# DAC.net
KiCad netlist of a schematic drawn in Altium Designer
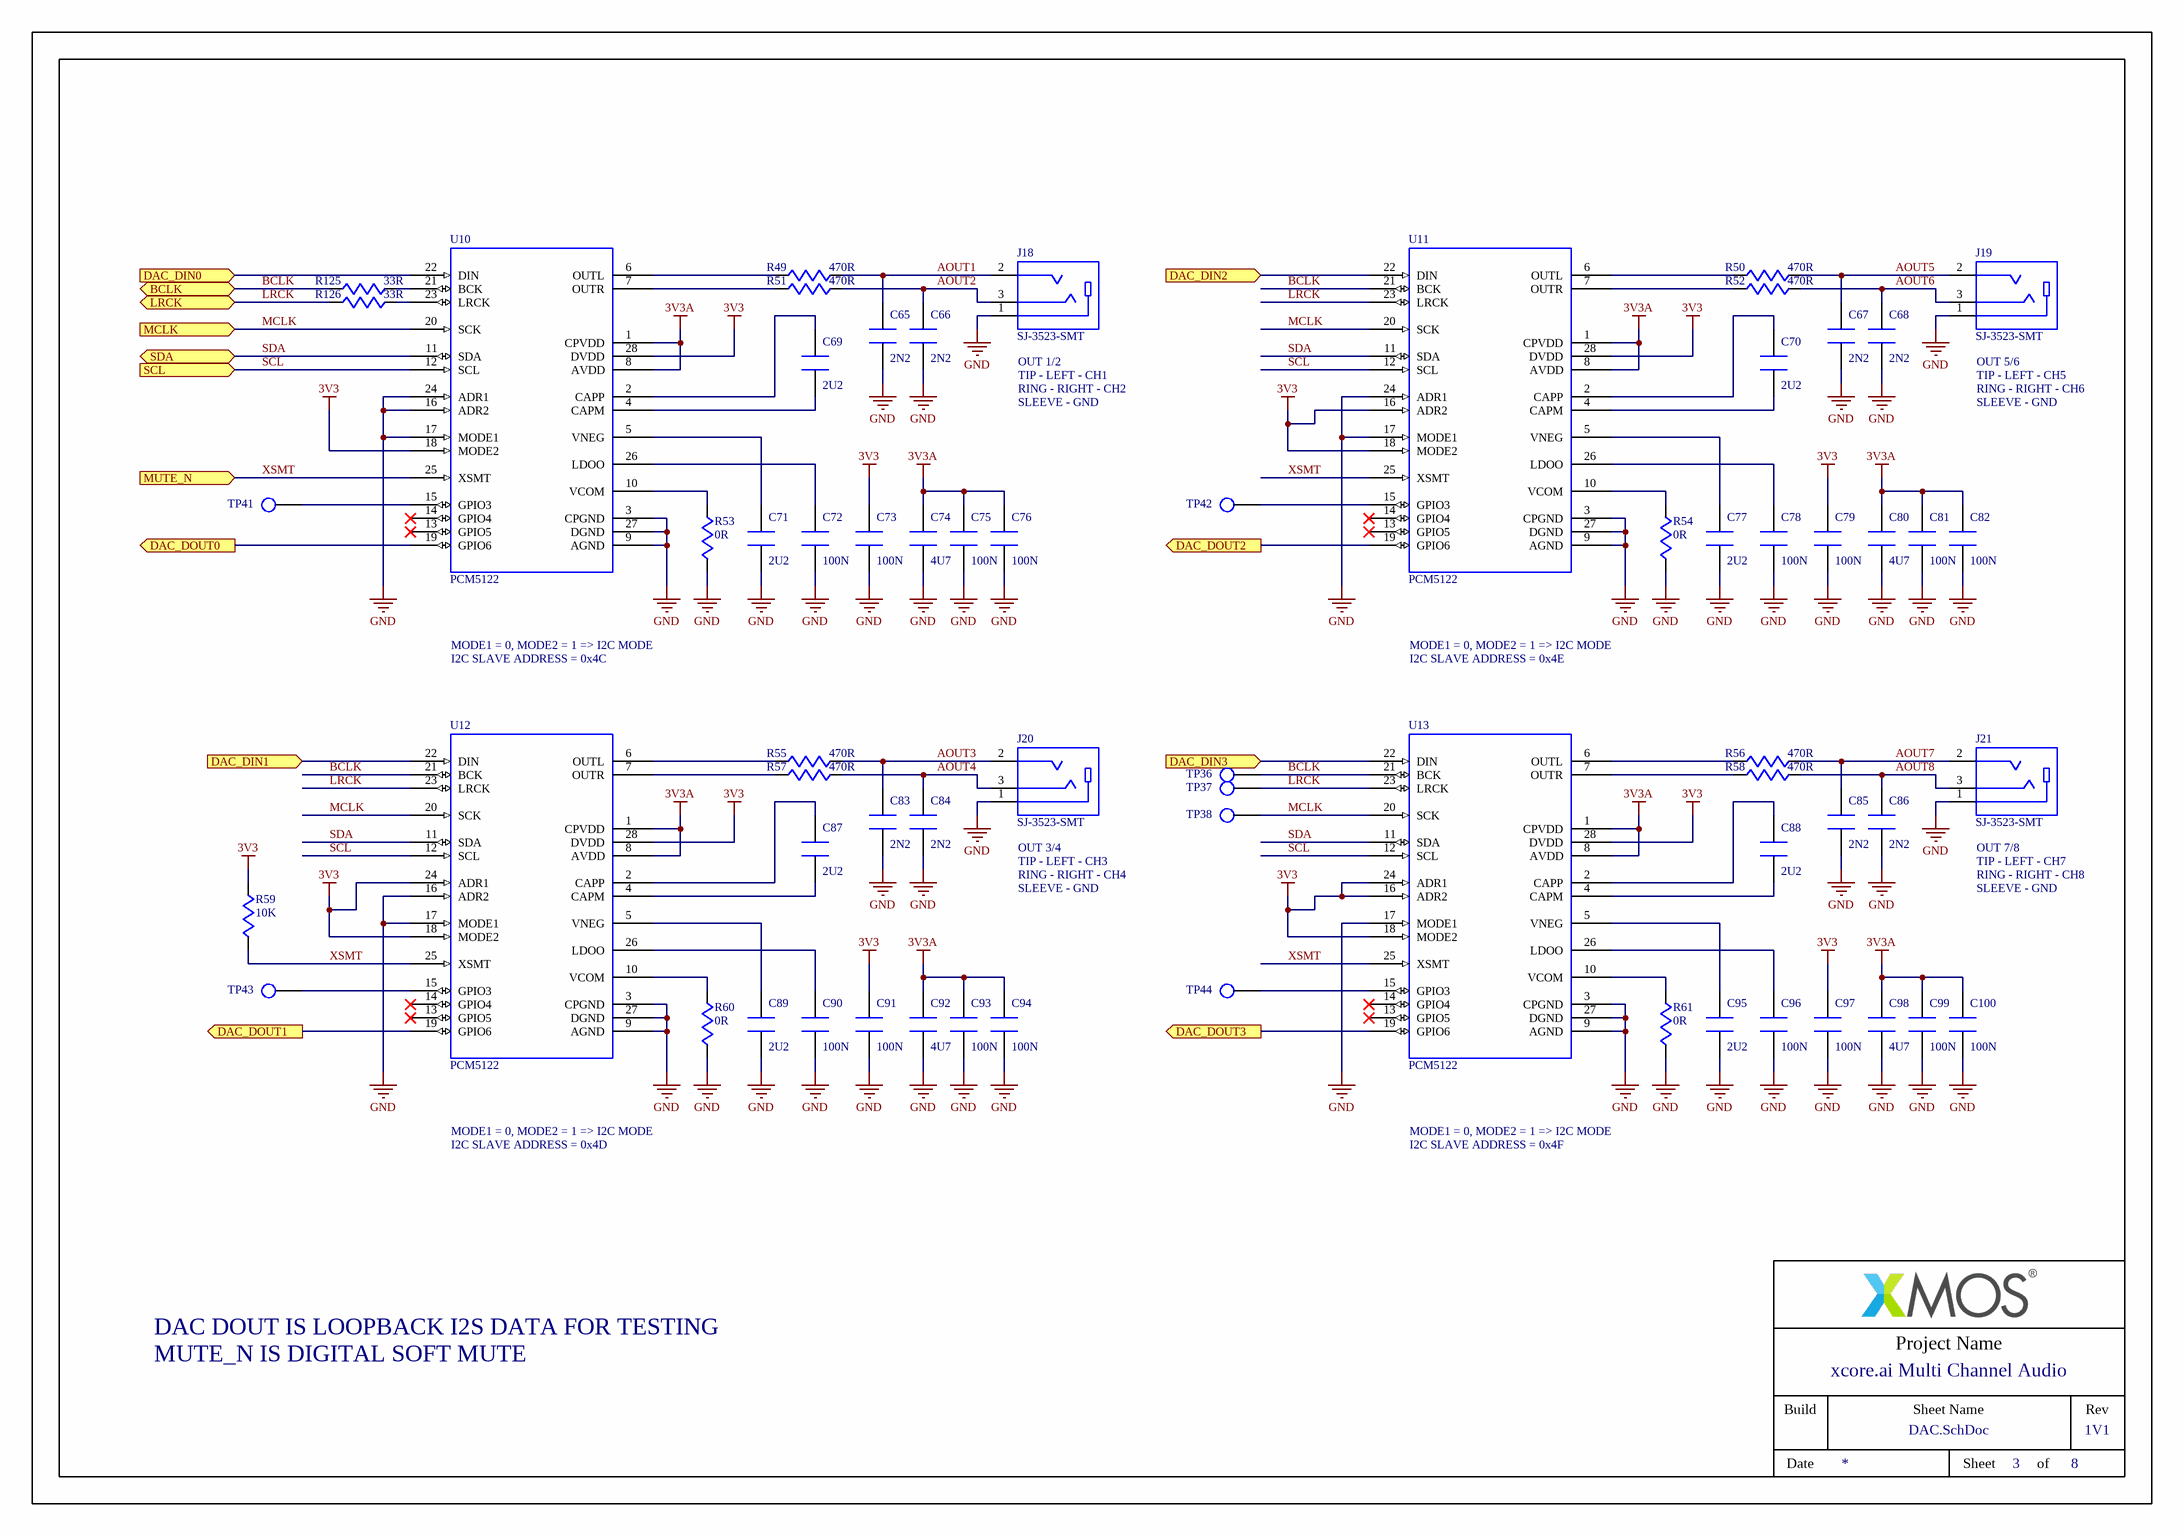
[diagram p0: DAC.SchDoc]

(export (version "E")
  (design (tool "Eeschema 10.0.6"))
  (components
    (comp (ref "C65")
      (value "2N2")
      (footprint "CAPC1608X90N")
      (description "CHIP CAPACITOR, CERAMIC, 2.2NF, 50V, 5%, NP0, 0603")
      (fields (field (name "PART NUMBER") "STD-06-0063") (field (name "TOLERANCE") "5%"))
      (libsource (lib "JG_StandardLibrary") (part "CAP_NP"))
    )
    (comp (ref "C66")
      (value "2N2")
      (footprint "CAPC1608X90N")
      (description "CHIP CAPACITOR, CERAMIC, 2.2NF, 50V, 5%, NP0, 0603")
      (fields (field (name "PART NUMBER") "STD-06-0063") (field (name "TOLERANCE") "5%"))
      (libsource (lib "JG_StandardLibrary") (part "CAP_NP"))
    )
    (comp (ref "C67")
      (value "2N2")
      (footprint "CAPC1608X90N")
      (description "CHIP CAPACITOR, CERAMIC, 2.2NF, 50V, 5%, NP0, 0603")
      (fields (field (name "PART NUMBER") "STD-06-0063") (field (name "TOLERANCE") "5%"))
      (libsource (lib "JG_StandardLibrary") (part "CAP_NP"))
    )
    (comp (ref "C68")
      (value "2N2")
      (footprint "CAPC1608X90N")
      (description "CHIP CAPACITOR, CERAMIC, 2.2NF, 50V, 5%, NP0, 0603")
      (fields (field (name "PART NUMBER") "STD-06-0063") (field (name "TOLERANCE") "5%"))
      (libsource (lib "JG_StandardLibrary") (part "CAP_NP"))
    )
    (comp (ref "C69")
      (value "2U2")
      (footprint "CAPC1608X90N")
      (description "CHIP CAPACITOR, CERAMIC, 2.2UF, 16V, 10%, X5R, 0603")
      (fields (field (name "PART NUMBER") "STD-06-0152") (field (name "TOLERANCE") "10%"))
      (libsource (lib "JG_StandardLibrary") (part "CAP_NP"))
    )
    (comp (ref "C70")
      (value "2U2")
      (footprint "CAPC1608X90N")
      (description "CHIP CAPACITOR, CERAMIC, 2.2UF, 16V, 10%, X5R, 0603")
      (fields (field (name "PART NUMBER") "STD-06-0152") (field (name "TOLERANCE") "10%"))
      (libsource (lib "JG_StandardLibrary") (part "CAP_NP"))
    )
    (comp (ref "C71")
      (value "2U2")
      (footprint "CAPC1608X90N")
      (description "CHIP CAPACITOR, CERAMIC, 2.2UF, 16V, 10%, X5R, 0603")
      (fields (field (name "PART NUMBER") "STD-06-0152") (field (name "TOLERANCE") "10%"))
      (libsource (lib "JG_StandardLibrary") (part "CAP_NP"))
    )
    (comp (ref "C72")
      (value "100N")
      (footprint "CAPC1005X55N")
      (description "CHIP CAPACITOR, CERAMIC, 100NF, 16V, 10%, X7R, 0402")
      (fields (field (name "PART NUMBER") "STD-06-0048") (field (name "TOLERANCE") "10%"))
      (libsource (lib "JG_StandardLibrary") (part "CAP_NP"))
    )
    (comp (ref "C73")
      (value "100N")
      (footprint "CAPC1005X55N")
      (description "CHIP CAPACITOR, CERAMIC, 100NF, 16V, 10%, X7R, 0402")
      (fields (field (name "PART NUMBER") "STD-06-0048") (field (name "TOLERANCE") "10%"))
      (libsource (lib "JG_StandardLibrary") (part "CAP_NP"))
    )
    (comp (ref "C74")
      (value "4U7")
      (footprint "CAPC1608X90N")
      (description "CHIP CAPACITOR, CERAMIC, 4.7UF, 16V, 10%, X5R, 0603")
      (fields (field (name "PART NUMBER") "STD-06-0151") (field (name "TOLERANCE") "10%"))
      (libsource (lib "JG_StandardLibrary") (part "CAP_NP"))
    )
    (comp (ref "C75")
      (value "100N")
      (footprint "CAPC1005X55N")
      (description "CHIP CAPACITOR, CERAMIC, 100NF, 16V, 10%, X7R, 0402")
      (fields (field (name "PART NUMBER") "STD-06-0048") (field (name "TOLERANCE") "10%"))
      (libsource (lib "JG_StandardLibrary") (part "CAP_NP"))
    )
    (comp (ref "C76")
      (value "100N")
      (footprint "CAPC1005X55N")
      (description "CHIP CAPACITOR, CERAMIC, 100NF, 16V, 10%, X7R, 0402")
      (fields (field (name "PART NUMBER") "STD-06-0048") (field (name "TOLERANCE") "10%"))
      (libsource (lib "JG_StandardLibrary") (part "CAP_NP"))
    )
    (comp (ref "C77")
      (value "2U2")
      (footprint "CAPC1608X90N")
      (description "CHIP CAPACITOR, CERAMIC, 2.2UF, 16V, 10%, X5R, 0603")
      (fields (field (name "PART NUMBER") "STD-06-0152") (field (name "TOLERANCE") "10%"))
      (libsource (lib "JG_StandardLibrary") (part "CAP_NP"))
    )
    (comp (ref "C78")
      (value "100N")
      (footprint "CAPC1005X55N")
      (description "CHIP CAPACITOR, CERAMIC, 100NF, 16V, 10%, X7R, 0402")
      (fields (field (name "PART NUMBER") "STD-06-0048") (field (name "TOLERANCE") "10%"))
      (libsource (lib "JG_StandardLibrary") (part "CAP_NP"))
    )
    (comp (ref "C79")
      (value "100N")
      (footprint "CAPC1005X55N")
      (description "CHIP CAPACITOR, CERAMIC, 100NF, 16V, 10%, X7R, 0402")
      (fields (field (name "PART NUMBER") "STD-06-0048") (field (name "TOLERANCE") "10%"))
      (libsource (lib "JG_StandardLibrary") (part "CAP_NP"))
    )
    (comp (ref "C80")
      (value "4U7")
      (footprint "CAPC1608X90N")
      (description "CHIP CAPACITOR, CERAMIC, 4.7UF, 16V, 10%, X5R, 0603")
      (fields (field (name "PART NUMBER") "STD-06-0151") (field (name "TOLERANCE") "10%"))
      (libsource (lib "JG_StandardLibrary") (part "CAP_NP"))
    )
    (comp (ref "C81")
      (value "100N")
      (footprint "CAPC1005X55N")
      (description "CHIP CAPACITOR, CERAMIC, 100NF, 16V, 10%, X7R, 0402")
      (fields (field (name "PART NUMBER") "STD-06-0048") (field (name "TOLERANCE") "10%"))
      (libsource (lib "JG_StandardLibrary") (part "CAP_NP"))
    )
    (comp (ref "C82")
      (value "100N")
      (footprint "CAPC1005X55N")
      (description "CHIP CAPACITOR, CERAMIC, 100NF, 16V, 10%, X7R, 0402")
      (fields (field (name "PART NUMBER") "STD-06-0048") (field (name "TOLERANCE") "10%"))
      (libsource (lib "JG_StandardLibrary") (part "CAP_NP"))
    )
    (comp (ref "C83")
      (value "2N2")
      (footprint "CAPC1608X90N")
      (description "CHIP CAPACITOR, CERAMIC, 2.2NF, 50V, 5%, NP0, 0603")
      (fields (field (name "PART NUMBER") "STD-06-0063") (field (name "TOLERANCE") "5%"))
      (libsource (lib "JG_StandardLibrary") (part "CAP_NP"))
    )
    (comp (ref "C84")
      (value "2N2")
      (footprint "CAPC1608X90N")
      (description "CHIP CAPACITOR, CERAMIC, 2.2NF, 50V, 5%, NP0, 0603")
      (fields (field (name "PART NUMBER") "STD-06-0063") (field (name "TOLERANCE") "5%"))
      (libsource (lib "JG_StandardLibrary") (part "CAP_NP"))
    )
    (comp (ref "C85")
      (value "2N2")
      (footprint "CAPC1608X90N")
      (description "CHIP CAPACITOR, CERAMIC, 2.2NF, 50V, 5%, NP0, 0603")
      (fields (field (name "PART NUMBER") "STD-06-0063") (field (name "TOLERANCE") "5%"))
      (libsource (lib "JG_StandardLibrary") (part "CAP_NP"))
    )
    (comp (ref "C86")
      (value "2N2")
      (footprint "CAPC1608X90N")
      (description "CHIP CAPACITOR, CERAMIC, 2.2NF, 50V, 5%, NP0, 0603")
      (fields (field (name "PART NUMBER") "STD-06-0063") (field (name "TOLERANCE") "5%"))
      (libsource (lib "JG_StandardLibrary") (part "CAP_NP"))
    )
    (comp (ref "C87")
      (value "2U2")
      (footprint "CAPC1608X90N")
      (description "CHIP CAPACITOR, CERAMIC, 2.2UF, 16V, 10%, X5R, 0603")
      (fields (field (name "PART NUMBER") "STD-06-0152") (field (name "TOLERANCE") "10%"))
      (libsource (lib "JG_StandardLibrary") (part "CAP_NP"))
    )
    (comp (ref "C88")
      (value "2U2")
      (footprint "CAPC1608X90N")
      (description "CHIP CAPACITOR, CERAMIC, 2.2UF, 16V, 10%, X5R, 0603")
      (fields (field (name "PART NUMBER") "STD-06-0152") (field (name "TOLERANCE") "10%"))
      (libsource (lib "JG_StandardLibrary") (part "CAP_NP"))
    )
    (comp (ref "C89")
      (value "2U2")
      (footprint "CAPC1608X90N")
      (description "CHIP CAPACITOR, CERAMIC, 2.2UF, 16V, 10%, X5R, 0603")
      (fields (field (name "PART NUMBER") "STD-06-0152") (field (name "TOLERANCE") "10%"))
      (libsource (lib "JG_StandardLibrary") (part "CAP_NP"))
    )
    (comp (ref "C90")
      (value "100N")
      (footprint "CAPC1005X55N")
      (description "CHIP CAPACITOR, CERAMIC, 100NF, 16V, 10%, X7R, 0402")
      (fields (field (name "PART NUMBER") "STD-06-0048") (field (name "TOLERANCE") "10%"))
      (libsource (lib "JG_StandardLibrary") (part "CAP_NP"))
    )
    (comp (ref "C91")
      (value "100N")
      (footprint "CAPC1005X55N")
      (description "CHIP CAPACITOR, CERAMIC, 100NF, 16V, 10%, X7R, 0402")
      (fields (field (name "PART NUMBER") "STD-06-0048") (field (name "TOLERANCE") "10%"))
      (libsource (lib "JG_StandardLibrary") (part "CAP_NP"))
    )
    (comp (ref "C92")
      (value "4U7")
      (footprint "CAPC1608X90N")
      (description "CHIP CAPACITOR, CERAMIC, 4.7UF, 16V, 10%, X5R, 0603")
      (fields (field (name "PART NUMBER") "STD-06-0151") (field (name "TOLERANCE") "10%"))
      (libsource (lib "JG_StandardLibrary") (part "CAP_NP"))
    )
    (comp (ref "C93")
      (value "100N")
      (footprint "CAPC1005X55N")
      (description "CHIP CAPACITOR, CERAMIC, 100NF, 16V, 10%, X7R, 0402")
      (fields (field (name "PART NUMBER") "STD-06-0048") (field (name "TOLERANCE") "10%"))
      (libsource (lib "JG_StandardLibrary") (part "CAP_NP"))
    )
    (comp (ref "C94")
      (value "100N")
      (footprint "CAPC1005X55N")
      (description "CHIP CAPACITOR, CERAMIC, 100NF, 16V, 10%, X7R, 0402")
      (fields (field (name "PART NUMBER") "STD-06-0048") (field (name "TOLERANCE") "10%"))
      (libsource (lib "JG_StandardLibrary") (part "CAP_NP"))
    )
    (comp (ref "C95")
      (value "2U2")
      (footprint "CAPC1608X90N")
      (description "CHIP CAPACITOR, CERAMIC, 2.2UF, 16V, 10%, X5R, 0603")
      (fields (field (name "PART NUMBER") "STD-06-0152") (field (name "TOLERANCE") "10%"))
      (libsource (lib "JG_StandardLibrary") (part "CAP_NP"))
    )
    (comp (ref "C96")
      (value "100N")
      (footprint "CAPC1005X55N")
      (description "CHIP CAPACITOR, CERAMIC, 100NF, 16V, 10%, X7R, 0402")
      (fields (field (name "PART NUMBER") "STD-06-0048") (field (name "TOLERANCE") "10%"))
      (libsource (lib "JG_StandardLibrary") (part "CAP_NP"))
    )
    (comp (ref "C97")
      (value "100N")
      (footprint "CAPC1005X55N")
      (description "CHIP CAPACITOR, CERAMIC, 100NF, 16V, 10%, X7R, 0402")
      (fields (field (name "PART NUMBER") "STD-06-0048") (field (name "TOLERANCE") "10%"))
      (libsource (lib "JG_StandardLibrary") (part "CAP_NP"))
    )
    (comp (ref "C98")
      (value "4U7")
      (footprint "CAPC1608X90N")
      (description "CHIP CAPACITOR, CERAMIC, 4.7UF, 16V, 10%, X5R, 0603")
      (fields (field (name "PART NUMBER") "STD-06-0151") (field (name "TOLERANCE") "10%"))
      (libsource (lib "JG_StandardLibrary") (part "CAP_NP"))
    )
    (comp (ref "C99")
      (value "100N")
      (footprint "CAPC1005X55N")
      (description "CHIP CAPACITOR, CERAMIC, 100NF, 16V, 10%, X7R, 0402")
      (fields (field (name "PART NUMBER") "STD-06-0048") (field (name "TOLERANCE") "10%"))
      (libsource (lib "JG_StandardLibrary") (part "CAP_NP"))
    )
    (comp (ref "C100")
      (value "100N")
      (footprint "CAPC1005X55N")
      (description "CHIP CAPACITOR, CERAMIC, 100NF, 16V, 10%, X7R, 0402")
      (fields (field (name "PART NUMBER") "STD-06-0048") (field (name "TOLERANCE") "10%"))
      (libsource (lib "JG_StandardLibrary") (part "CAP_NP"))
    )
    (comp (ref "J18")
      (value "SJ-3523-SMT")
      (footprint "CON_CUI_SJ3523")
      (description "TRS jack, 3.5mm, SMD")
      (fields (field (name "PART NUMBER") "GEN-01-0021") (field (name "MANUFACTURER") "CUI"))
      (libsource (lib "JG_GeneralLibrary") (part "TRS_JACK_3_A"))
    )
    (comp (ref "J19")
      (value "SJ-3523-SMT")
      (footprint "CON_CUI_SJ3523")
      (description "TRS jack, 3.5mm, SMD")
      (fields (field (name "PART NUMBER") "GEN-01-0021") (field (name "MANUFACTURER") "CUI"))
      (libsource (lib "JG_GeneralLibrary") (part "TRS_JACK_3_A"))
    )
    (comp (ref "J20")
      (value "SJ-3523-SMT")
      (footprint "CON_CUI_SJ3523")
      (description "TRS jack, 3.5mm, SMD")
      (fields (field (name "PART NUMBER") "GEN-01-0021") (field (name "MANUFACTURER") "CUI"))
      (libsource (lib "JG_GeneralLibrary") (part "TRS_JACK_3_A"))
    )
    (comp (ref "J21")
      (value "SJ-3523-SMT")
      (footprint "CON_CUI_SJ3523")
      (description "TRS jack, 3.5mm, SMD")
      (fields (field (name "PART NUMBER") "GEN-01-0021") (field (name "MANUFACTURER") "CUI"))
      (libsource (lib "JG_GeneralLibrary") (part "TRS_JACK_3_A"))
    )
    (comp (ref "R49")
      (value "470R")
      (footprint "RESC1608X55N")
      (description "CHIP RESISTOR, 470 OHM, 0.1W, 1%, 0603")
      (fields (field (name "PART NUMBER") "STD-02-0054") (field (name "TOLERANCE") "1%"))
      (libsource (lib "JG_StandardLibrary") (part "RES"))
    )
    (comp (ref "R50")
      (value "470R")
      (footprint "RESC1608X55N")
      (description "CHIP RESISTOR, 470 OHM, 0.1W, 1%, 0603")
      (fields (field (name "PART NUMBER") "STD-02-0054") (field (name "TOLERANCE") "1%"))
      (libsource (lib "JG_StandardLibrary") (part "RES"))
    )
    (comp (ref "R51")
      (value "470R")
      (footprint "RESC1608X55N")
      (description "CHIP RESISTOR, 470 OHM, 0.1W, 1%, 0603")
      (fields (field (name "PART NUMBER") "STD-02-0054") (field (name "TOLERANCE") "1%"))
      (libsource (lib "JG_StandardLibrary") (part "RES"))
    )
    (comp (ref "R52")
      (value "470R")
      (footprint "RESC1608X55N")
      (description "CHIP RESISTOR, 470 OHM, 0.1W, 1%, 0603")
      (fields (field (name "PART NUMBER") "STD-02-0054") (field (name "TOLERANCE") "1%"))
      (libsource (lib "JG_StandardLibrary") (part "RES"))
    )
    (comp (ref "R53")
      (value "0R")
      (footprint "RESC1608X55N")
      (description "CHIP RESISTOR, ZERO OHM JUMPER, 1A, 0603")
      (fields (field (name "PART NUMBER") "STD-02-0001") (field (name "TOLERANCE") "NA"))
      (libsource (lib "JG_StandardLibrary") (part "RES"))
    )
    (comp (ref "R54")
      (value "0R")
      (footprint "RESC1608X55N")
      (description "CHIP RESISTOR, ZERO OHM JUMPER, 1A, 0603")
      (fields (field (name "PART NUMBER") "STD-02-0001") (field (name "TOLERANCE") "NA"))
      (libsource (lib "JG_StandardLibrary") (part "RES"))
    )
    (comp (ref "R55")
      (value "470R")
      (footprint "RESC1608X55N")
      (description "CHIP RESISTOR, 470 OHM, 0.1W, 1%, 0603")
      (fields (field (name "PART NUMBER") "STD-02-0054") (field (name "TOLERANCE") "1%"))
      (libsource (lib "JG_StandardLibrary") (part "RES"))
    )
    (comp (ref "R56")
      (value "470R")
      (footprint "RESC1608X55N")
      (description "CHIP RESISTOR, 470 OHM, 0.1W, 1%, 0603")
      (fields (field (name "PART NUMBER") "STD-02-0054") (field (name "TOLERANCE") "1%"))
      (libsource (lib "JG_StandardLibrary") (part "RES"))
    )
    (comp (ref "R57")
      (value "470R")
      (footprint "RESC1608X55N")
      (description "CHIP RESISTOR, 470 OHM, 0.1W, 1%, 0603")
      (fields (field (name "PART NUMBER") "STD-02-0054") (field (name "TOLERANCE") "1%"))
      (libsource (lib "JG_StandardLibrary") (part "RES"))
    )
    (comp (ref "R58")
      (value "470R")
      (footprint "RESC1608X55N")
      (description "CHIP RESISTOR, 470 OHM, 0.1W, 1%, 0603")
      (fields (field (name "PART NUMBER") "STD-02-0054") (field (name "TOLERANCE") "1%"))
      (libsource (lib "JG_StandardLibrary") (part "RES"))
    )
    (comp (ref "R59")
      (value "10K")
      (footprint "RESC1608X55N")
      (description "CHIP RESISTOR, 10K OHM, 0.1W, 1%, 0603")
      (fields (field (name "PART NUMBER") "STD-02-0086") (field (name "TOLERANCE") "1%"))
      (libsource (lib "JG_StandardLibrary") (part "RES"))
    )
    (comp (ref "R60")
      (value "0R")
      (footprint "RESC1608X55N")
      (description "CHIP RESISTOR, ZERO OHM JUMPER, 1A, 0603")
      (fields (field (name "PART NUMBER") "STD-02-0001") (field (name "TOLERANCE") "NA"))
      (libsource (lib "JG_StandardLibrary") (part "RES"))
    )
    (comp (ref "R61")
      (value "0R")
      (footprint "RESC1608X55N")
      (description "CHIP RESISTOR, ZERO OHM JUMPER, 1A, 0603")
      (fields (field (name "PART NUMBER") "STD-02-0001") (field (name "TOLERANCE") "NA"))
      (libsource (lib "JG_StandardLibrary") (part "RES"))
    )
    (comp (ref "R125")
      (value "33R")
      (footprint "RESC1608X55N")
      (description "CHIP RESISTOR, 33 OHM, 0.1W, 1%, 0603")
      (fields (field (name "PART NUMBER") "STD-02-0026") (field (name "TOLERANCE") "1%"))
      (libsource (lib "JG_StandardLibrary") (part "RES"))
    )
    (comp (ref "R126")
      (value "33R")
      (footprint "RESC1608X55N")
      (description "CHIP RESISTOR, 33 OHM, 0.1W, 1%, 0603")
      (fields (field (name "PART NUMBER") "STD-02-0026") (field (name "TOLERANCE") "1%"))
      (libsource (lib "JG_StandardLibrary") (part "RES"))
    )
    (comp (ref "TP36")
      (value "TESTPOINT")
      (footprint "TESTPOINT_SMD_0.9MM_L")
      (description "Testpoint, SMD, 0.9mm")
      (fields (field (name "PART NUMBER") "GEN-24-0019") (field (name "MANUFACTURER") "NA"))
      (libsource (lib "JG_GeneralLibrary") (part "TESTPOINT"))
    )
    (comp (ref "TP37")
      (value "TESTPOINT")
      (footprint "TESTPOINT_SMD_0.9MM_L")
      (description "Testpoint, SMD, 0.9mm")
      (fields (field (name "PART NUMBER") "GEN-24-0019") (field (name "MANUFACTURER") "NA"))
      (libsource (lib "JG_GeneralLibrary") (part "TESTPOINT"))
    )
    (comp (ref "TP38")
      (value "TESTPOINT")
      (footprint "TESTPOINT_SMD_0.9MM_L")
      (description "Testpoint, SMD, 0.9mm")
      (fields (field (name "PART NUMBER") "GEN-24-0019") (field (name "MANUFACTURER") "NA"))
      (libsource (lib "JG_GeneralLibrary") (part "TESTPOINT"))
    )
    (comp (ref "TP41")
      (value "TESTPOINT")
      (footprint "TESTPOINT_SMD_0.9MM_L")
      (description "Testpoint, SMD, 0.9mm")
      (fields (field (name "PART NUMBER") "GEN-24-0019") (field (name "MANUFACTURER") "NA"))
      (libsource (lib "JG_GeneralLibrary") (part "TESTPOINT"))
    )
    (comp (ref "TP42")
      (value "TESTPOINT")
      (footprint "TESTPOINT_SMD_0.9MM_L")
      (description "Testpoint, SMD, 0.9mm")
      (fields (field (name "PART NUMBER") "GEN-24-0019") (field (name "MANUFACTURER") "NA"))
      (libsource (lib "JG_GeneralLibrary") (part "TESTPOINT"))
    )
    (comp (ref "TP43")
      (value "TESTPOINT")
      (footprint "TESTPOINT_SMD_0.9MM_L")
      (description "Testpoint, SMD, 0.9mm")
      (fields (field (name "PART NUMBER") "GEN-24-0019") (field (name "MANUFACTURER") "NA"))
      (libsource (lib "JG_GeneralLibrary") (part "TESTPOINT"))
    )
    (comp (ref "TP44")
      (value "TESTPOINT")
      (footprint "TESTPOINT_SMD_0.9MM_L")
      (description "Testpoint, SMD, 0.9mm")
      (fields (field (name "PART NUMBER") "GEN-24-0019") (field (name "MANUFACTURER") "NA"))
      (libsource (lib "JG_GeneralLibrary") (part "TESTPOINT"))
    )
    (comp (ref "U10")
      (value "PCM5122")
      (footprint "SOP65P640X120-28N")
      (description "Stereo Audio DAC, 32 bit/384kHz, 112dB SNR, PLL, 2Vrms Output, TSSOP28")
      (fields (field (name "PART NUMBER") "GEN-06-0001") (field (name "MANUFACTURER") "Texas Instruments"))
      (libsource (lib "JG_GeneralLibrary") (part "TI_PCM5122_I2C"))
    )
    (comp (ref "U11")
      (value "PCM5122")
      (footprint "SOP65P640X120-28N")
      (description "Stereo Audio DAC, 32 bit/384kHz, 112dB SNR, PLL, 2Vrms Output, TSSOP28")
      (fields (field (name "PART NUMBER") "GEN-06-0001") (field (name "MANUFACTURER") "Texas Instruments"))
      (libsource (lib "JG_GeneralLibrary") (part "TI_PCM5122_I2C"))
    )
    (comp (ref "U12")
      (value "PCM5122")
      (footprint "SOP65P640X120-28N")
      (description "Stereo Audio DAC, 32 bit/384kHz, 112dB SNR, PLL, 2Vrms Output, TSSOP28")
      (fields (field (name "PART NUMBER") "GEN-06-0001") (field (name "MANUFACTURER") "Texas Instruments"))
      (libsource (lib "JG_GeneralLibrary") (part "TI_PCM5122_I2C"))
    )
    (comp (ref "U13")
      (value "PCM5122")
      (footprint "SOP65P640X120-28N")
      (description "Stereo Audio DAC, 32 bit/384kHz, 112dB SNR, PLL, 2Vrms Output, TSSOP28")
      (fields (field (name "PART NUMBER") "GEN-06-0001") (field (name "MANUFACTURER") "Texas Instruments"))
      (libsource (lib "JG_GeneralLibrary") (part "TI_PCM5122_I2C"))
    )
  )
  (nets
    (net (code "1") (name "/AOUT1") (class "Default")
      (node (ref "C65") (pin "1") (pinfunction "1_1") (pintype "passive"))
      (node (ref "J18") (pin "2") (pinfunction "2_2") (pintype "passive"))
      (node (ref "R49") (pin "2") (pinfunction "2_2") (pintype "passive"))
    )
    (net (code "2") (name "/AOUT2") (class "Default")
      (node (ref "C66") (pin "1") (pinfunction "1_1") (pintype "passive"))
      (node (ref "J18") (pin "3") (pinfunction "3_3") (pintype "passive"))
      (node (ref "R51") (pin "2") (pinfunction "2_2") (pintype "passive"))
    )
    (net (code "3") (name "/AOUT3") (class "Default")
      (node (ref "C83") (pin "1") (pinfunction "1_1") (pintype "passive"))
      (node (ref "J20") (pin "2") (pinfunction "2_2") (pintype "passive"))
      (node (ref "R55") (pin "2") (pinfunction "2_2") (pintype "passive"))
    )
    (net (code "4") (name "/AOUT4") (class "Default")
      (node (ref "C84") (pin "1") (pinfunction "1_1") (pintype "passive"))
      (node (ref "J20") (pin "3") (pinfunction "3_3") (pintype "passive"))
      (node (ref "R57") (pin "2") (pinfunction "2_2") (pintype "passive"))
    )
    (net (code "5") (name "/AOUT5") (class "Default")
      (node (ref "C67") (pin "1") (pinfunction "1_1") (pintype "passive"))
      (node (ref "J19") (pin "2") (pinfunction "2_2") (pintype "passive"))
      (node (ref "R50") (pin "2") (pinfunction "2_2") (pintype "passive"))
    )
    (net (code "6") (name "/AOUT6") (class "Default")
      (node (ref "C68") (pin "1") (pinfunction "1_1") (pintype "passive"))
      (node (ref "J19") (pin "3") (pinfunction "3_3") (pintype "passive"))
      (node (ref "R52") (pin "2") (pinfunction "2_2") (pintype "passive"))
    )
    (net (code "7") (name "/AOUT7") (class "Default")
      (node (ref "C85") (pin "1") (pinfunction "1_1") (pintype "passive"))
      (node (ref "J21") (pin "2") (pinfunction "2_2") (pintype "passive"))
      (node (ref "R56") (pin "2") (pinfunction "2_2") (pintype "passive"))
    )
    (net (code "8") (name "/AOUT8") (class "Default")
      (node (ref "C86") (pin "1") (pinfunction "1_1") (pintype "passive"))
      (node (ref "J21") (pin "3") (pinfunction "3_3") (pintype "passive"))
      (node (ref "R58") (pin "2") (pinfunction "2_2") (pintype "passive"))
    )
    (net (code "9") (name "/BCLK") (class "Default")
      (node (ref "R125") (pin "1") (pinfunction "1_1") (pintype "passive"))
      (node (ref "TP36") (pin "1") (pinfunction "1_1") (pintype "passive"))
      (node (ref "U11") (pin "21") (pinfunction "BCK_21") (pintype "bidirectional"))
      (node (ref "U12") (pin "21") (pinfunction "BCK_21") (pintype "bidirectional"))
      (node (ref "U13") (pin "21") (pinfunction "BCK_21") (pintype "bidirectional"))
    )
    (net (code "10") (name "/DAC_DIN0") (class "Default")
      (node (ref "U10") (pin "22") (pinfunction "DIN_22") (pintype "input"))
    )
    (net (code "11") (name "/DAC_DIN1") (class "Default")
      (node (ref "U12") (pin "22") (pinfunction "DIN_22") (pintype "input"))
    )
    (net (code "12") (name "/DAC_DIN2") (class "Default")
      (node (ref "U11") (pin "22") (pinfunction "DIN_22") (pintype "input"))
    )
    (net (code "13") (name "/DAC_DIN3") (class "Default")
      (node (ref "U13") (pin "22") (pinfunction "DIN_22") (pintype "input"))
    )
    (net (code "14") (name "/DAC_DOUT0") (class "Default")
      (node (ref "U10") (pin "19") (pinfunction "GPIO6_19") (pintype "bidirectional"))
    )
    (net (code "15") (name "/DAC_DOUT1") (class "Default")
      (node (ref "U12") (pin "19") (pinfunction "GPIO6_19") (pintype "bidirectional"))
    )
    (net (code "16") (name "/DAC_DOUT2") (class "Default")
      (node (ref "U11") (pin "19") (pinfunction "GPIO6_19") (pintype "bidirectional"))
    )
    (net (code "17") (name "/DAC_DOUT3") (class "Default")
      (node (ref "U13") (pin "19") (pinfunction "GPIO6_19") (pintype "bidirectional"))
    )
    (net (code "18") (name "/LRCK") (class "Default")
      (node (ref "R126") (pin "1") (pinfunction "1_1") (pintype "passive"))
      (node (ref "TP37") (pin "1") (pinfunction "1_1") (pintype "passive"))
      (node (ref "U11") (pin "23") (pinfunction "LRCK_23") (pintype "bidirectional"))
      (node (ref "U12") (pin "23") (pinfunction "LRCK_23") (pintype "bidirectional"))
      (node (ref "U13") (pin "23") (pinfunction "LRCK_23") (pintype "bidirectional"))
    )
    (net (code "19") (name "/MCLK") (class "Default")
      (node (ref "TP38") (pin "1") (pinfunction "1_1") (pintype "passive"))
      (node (ref "U10") (pin "20") (pinfunction "SCK_20") (pintype "input"))
      (node (ref "U11") (pin "20") (pinfunction "SCK_20") (pintype "input"))
      (node (ref "U12") (pin "20") (pinfunction "SCK_20") (pintype "input"))
      (node (ref "U13") (pin "20") (pinfunction "SCK_20") (pintype "input"))
    )
    (net (code "20") (name "/SCL") (class "Default")
      (node (ref "U10") (pin "12") (pinfunction "SCL_12") (pintype "input"))
      (node (ref "U11") (pin "12") (pinfunction "SCL_12") (pintype "input"))
      (node (ref "U12") (pin "12") (pinfunction "SCL_12") (pintype "input"))
      (node (ref "U13") (pin "12") (pinfunction "SCL_12") (pintype "input"))
    )
    (net (code "21") (name "/SDA") (class "Default")
      (node (ref "U10") (pin "11") (pinfunction "SDA_11") (pintype "bidirectional"))
      (node (ref "U11") (pin "11") (pinfunction "SDA_11") (pintype "bidirectional"))
      (node (ref "U12") (pin "11") (pinfunction "SDA_11") (pintype "bidirectional"))
      (node (ref "U13") (pin "11") (pinfunction "SDA_11") (pintype "bidirectional"))
    )
    (net (code "22") (name "/XSMT") (class "Default")
      (node (ref "R59") (pin "1") (pinfunction "1_1") (pintype "passive"))
      (node (ref "U10") (pin "25") (pinfunction "XSMT_25") (pintype "input"))
      (node (ref "U11") (pin "25") (pinfunction "XSMT_25") (pintype "input"))
      (node (ref "U12") (pin "25") (pinfunction "XSMT_25") (pintype "input"))
      (node (ref "U13") (pin "25") (pinfunction "XSMT_25") (pintype "input"))
    )
    (net (code "23") (name "3V3") (class "Default")
      (node (ref "C73") (pin "1") (pinfunction "1_1") (pintype "passive"))
      (node (ref "C79") (pin "1") (pinfunction "1_1") (pintype "passive"))
      (node (ref "C91") (pin "1") (pinfunction "1_1") (pintype "passive"))
      (node (ref "C97") (pin "1") (pinfunction "1_1") (pintype "passive"))
      (node (ref "R59") (pin "2") (pinfunction "2_2") (pintype "passive"))
      (node (ref "U10") (pin "18") (pinfunction "MODE2_18") (pintype "input"))
      (node (ref "U10") (pin "28") (pinfunction "DVDD_28") (pintype "power_in"))
      (node (ref "U11") (pin "16") (pinfunction "ADR2_16") (pintype "input"))
      (node (ref "U11") (pin "18") (pinfunction "MODE2_18") (pintype "input"))
      (node (ref "U11") (pin "28") (pinfunction "DVDD_28") (pintype "power_in"))
      (node (ref "U12") (pin "18") (pinfunction "MODE2_18") (pintype "input"))
      (node (ref "U12") (pin "24") (pinfunction "ADR1_24") (pintype "input"))
      (node (ref "U12") (pin "28") (pinfunction "DVDD_28") (pintype "power_in"))
      (node (ref "U13") (pin "16") (pinfunction "ADR2_16") (pintype "input"))
      (node (ref "U13") (pin "18") (pinfunction "MODE2_18") (pintype "input"))
      (node (ref "U13") (pin "24") (pinfunction "ADR1_24") (pintype "input"))
      (node (ref "U13") (pin "28") (pinfunction "DVDD_28") (pintype "power_in"))
    )
    (net (code "24") (name "3V3A") (class "Default")
      (node (ref "C100") (pin "1") (pinfunction "1_1") (pintype "passive"))
      (node (ref "C74") (pin "1") (pinfunction "1_1") (pintype "passive"))
      (node (ref "C75") (pin "1") (pinfunction "1_1") (pintype "passive"))
      (node (ref "C76") (pin "1") (pinfunction "1_1") (pintype "passive"))
      (node (ref "C80") (pin "1") (pinfunction "1_1") (pintype "passive"))
      (node (ref "C81") (pin "1") (pinfunction "1_1") (pintype "passive"))
      (node (ref "C82") (pin "1") (pinfunction "1_1") (pintype "passive"))
      (node (ref "C92") (pin "1") (pinfunction "1_1") (pintype "passive"))
      (node (ref "C93") (pin "1") (pinfunction "1_1") (pintype "passive"))
      (node (ref "C94") (pin "1") (pinfunction "1_1") (pintype "passive"))
      (node (ref "C98") (pin "1") (pinfunction "1_1") (pintype "passive"))
      (node (ref "C99") (pin "1") (pinfunction "1_1") (pintype "passive"))
      (node (ref "U10") (pin "1") (pinfunction "CPVDD_1") (pintype "power_in"))
      (node (ref "U10") (pin "8") (pinfunction "AVDD_8") (pintype "power_in"))
      (node (ref "U11") (pin "1") (pinfunction "CPVDD_1") (pintype "power_in"))
      (node (ref "U11") (pin "8") (pinfunction "AVDD_8") (pintype "power_in"))
      (node (ref "U12") (pin "1") (pinfunction "CPVDD_1") (pintype "power_in"))
      (node (ref "U12") (pin "8") (pinfunction "AVDD_8") (pintype "power_in"))
      (node (ref "U13") (pin "1") (pinfunction "CPVDD_1") (pintype "power_in"))
      (node (ref "U13") (pin "8") (pinfunction "AVDD_8") (pintype "power_in"))
    )
    (net (code "25") (name "GND") (class "Default")
      (node (ref "C100") (pin "2") (pinfunction "2_2") (pintype "passive"))
      (node (ref "C65") (pin "2") (pinfunction "2_2") (pintype "passive"))
      (node (ref "C66") (pin "2") (pinfunction "2_2") (pintype "passive"))
      (node (ref "C67") (pin "2") (pinfunction "2_2") (pintype "passive"))
      (node (ref "C68") (pin "2") (pinfunction "2_2") (pintype "passive"))
      (node (ref "C71") (pin "2") (pinfunction "2_2") (pintype "passive"))
      (node (ref "C72") (pin "2") (pinfunction "2_2") (pintype "passive"))
      (node (ref "C73") (pin "2") (pinfunction "2_2") (pintype "passive"))
      (node (ref "C74") (pin "2") (pinfunction "2_2") (pintype "passive"))
      (node (ref "C75") (pin "2") (pinfunction "2_2") (pintype "passive"))
      (node (ref "C76") (pin "2") (pinfunction "2_2") (pintype "passive"))
      (node (ref "C77") (pin "2") (pinfunction "2_2") (pintype "passive"))
      (node (ref "C78") (pin "2") (pinfunction "2_2") (pintype "passive"))
      (node (ref "C79") (pin "2") (pinfunction "2_2") (pintype "passive"))
      (node (ref "C80") (pin "2") (pinfunction "2_2") (pintype "passive"))
      (node (ref "C81") (pin "2") (pinfunction "2_2") (pintype "passive"))
      (node (ref "C82") (pin "2") (pinfunction "2_2") (pintype "passive"))
      (node (ref "C83") (pin "2") (pinfunction "2_2") (pintype "passive"))
      (node (ref "C84") (pin "2") (pinfunction "2_2") (pintype "passive"))
      (node (ref "C85") (pin "2") (pinfunction "2_2") (pintype "passive"))
      (node (ref "C86") (pin "2") (pinfunction "2_2") (pintype "passive"))
      (node (ref "C89") (pin "2") (pinfunction "2_2") (pintype "passive"))
      (node (ref "C90") (pin "2") (pinfunction "2_2") (pintype "passive"))
      (node (ref "C91") (pin "2") (pinfunction "2_2") (pintype "passive"))
      (node (ref "C92") (pin "2") (pinfunction "2_2") (pintype "passive"))
      (node (ref "C93") (pin "2") (pinfunction "2_2") (pintype "passive"))
      (node (ref "C94") (pin "2") (pinfunction "2_2") (pintype "passive"))
      (node (ref "C95") (pin "2") (pinfunction "2_2") (pintype "passive"))
      (node (ref "C96") (pin "2") (pinfunction "2_2") (pintype "passive"))
      (node (ref "C97") (pin "2") (pinfunction "2_2") (pintype "passive"))
      (node (ref "C98") (pin "2") (pinfunction "2_2") (pintype "passive"))
      (node (ref "C99") (pin "2") (pinfunction "2_2") (pintype "passive"))
      (node (ref "J18") (pin "1") (pinfunction "1_1") (pintype "passive"))
      (node (ref "J19") (pin "1") (pinfunction "1_1") (pintype "passive"))
      (node (ref "J20") (pin "1") (pinfunction "1_1") (pintype "passive"))
      (node (ref "J21") (pin "1") (pinfunction "1_1") (pintype "passive"))
      (node (ref "R53") (pin "1") (pinfunction "1_1") (pintype "passive"))
      (node (ref "R54") (pin "1") (pinfunction "1_1") (pintype "passive"))
      (node (ref "R60") (pin "1") (pinfunction "1_1") (pintype "passive"))
      (node (ref "R61") (pin "1") (pinfunction "1_1") (pintype "passive"))
      (node (ref "U10") (pin "16") (pinfunction "ADR2_16") (pintype "input"))
      (node (ref "U10") (pin "17") (pinfunction "MODE1_17") (pintype "input"))
      (node (ref "U10") (pin "24") (pinfunction "ADR1_24") (pintype "input"))
      (node (ref "U10") (pin "27") (pinfunction "DGND_27") (pintype "power_in"))
      (node (ref "U10") (pin "3") (pinfunction "CPGND_3") (pintype "power_in"))
      (node (ref "U10") (pin "9") (pinfunction "AGND_9") (pintype "power_in"))
      (node (ref "U11") (pin "17") (pinfunction "MODE1_17") (pintype "input"))
      (node (ref "U11") (pin "24") (pinfunction "ADR1_24") (pintype "input"))
      (node (ref "U11") (pin "27") (pinfunction "DGND_27") (pintype "power_in"))
      (node (ref "U11") (pin "3") (pinfunction "CPGND_3") (pintype "power_in"))
      (node (ref "U11") (pin "9") (pinfunction "AGND_9") (pintype "power_in"))
      (node (ref "U12") (pin "16") (pinfunction "ADR2_16") (pintype "input"))
      (node (ref "U12") (pin "17") (pinfunction "MODE1_17") (pintype "input"))
      (node (ref "U12") (pin "27") (pinfunction "DGND_27") (pintype "power_in"))
      (node (ref "U12") (pin "3") (pinfunction "CPGND_3") (pintype "power_in"))
      (node (ref "U12") (pin "9") (pinfunction "AGND_9") (pintype "power_in"))
      (node (ref "U13") (pin "17") (pinfunction "MODE1_17") (pintype "input"))
      (node (ref "U13") (pin "27") (pinfunction "DGND_27") (pintype "power_in"))
      (node (ref "U13") (pin "3") (pinfunction "CPGND_3") (pintype "power_in"))
      (node (ref "U13") (pin "9") (pinfunction "AGND_9") (pintype "power_in"))
    )
    (net (code "26") (name "Net-(U10-BCK)") (class "Default")
      (node (ref "R125") (pin "2") (pinfunction "2_2") (pintype "passive"))
      (node (ref "U10") (pin "21") (pinfunction "BCK_21") (pintype "bidirectional"))
    )
    (net (code "27") (name "Net-(U10-CAPM)") (class "Default")
      (node (ref "C69") (pin "2") (pinfunction "2_2") (pintype "passive"))
      (node (ref "U10") (pin "4") (pinfunction "CAPM_4") (pintype "power_in"))
    )
    (net (code "28") (name "Net-(U10-CAPP)") (class "Default")
      (node (ref "C69") (pin "1") (pinfunction "1_1") (pintype "passive"))
      (node (ref "U10") (pin "2") (pinfunction "CAPP_2") (pintype "power_in"))
    )
    (net (code "29") (name "Net-(U10-GPIO3)") (class "Default")
      (node (ref "TP41") (pin "1") (pinfunction "1_1") (pintype "passive"))
      (node (ref "U10") (pin "15") (pinfunction "GPIO3_15") (pintype "bidirectional"))
    )
    (net (code "30") (name "Net-(U10-LDOO)") (class "Default")
      (node (ref "C72") (pin "1") (pinfunction "1_1") (pintype "passive"))
      (node (ref "U10") (pin "26") (pinfunction "LDOO_26") (pintype "power_in"))
    )
    (net (code "31") (name "Net-(U10-LRCK)") (class "Default")
      (node (ref "R126") (pin "2") (pinfunction "2_2") (pintype "passive"))
      (node (ref "U10") (pin "23") (pinfunction "LRCK_23") (pintype "bidirectional"))
    )
    (net (code "32") (name "Net-(U10-OUTL)") (class "Default")
      (node (ref "R49") (pin "1") (pinfunction "1_1") (pintype "passive"))
      (node (ref "U10") (pin "6") (pinfunction "OUTL_6") (pintype "passive"))
    )
    (net (code "33") (name "Net-(U10-OUTR)") (class "Default")
      (node (ref "R51") (pin "1") (pinfunction "1_1") (pintype "passive"))
      (node (ref "U10") (pin "7") (pinfunction "OUTR_7") (pintype "passive"))
    )
    (net (code "34") (name "Net-(U10-VCOM)") (class "Default")
      (node (ref "R53") (pin "2") (pinfunction "2_2") (pintype "passive"))
      (node (ref "U10") (pin "10") (pinfunction "VCOM_10") (pintype "power_in"))
    )
    (net (code "35") (name "Net-(U10-VNEG)") (class "Default")
      (node (ref "C71") (pin "1") (pinfunction "1_1") (pintype "passive"))
      (node (ref "U10") (pin "5") (pinfunction "VNEG_5") (pintype "power_in"))
    )
    (net (code "36") (name "Net-(U11-CAPM)") (class "Default")
      (node (ref "C70") (pin "2") (pinfunction "2_2") (pintype "passive"))
      (node (ref "U11") (pin "4") (pinfunction "CAPM_4") (pintype "power_in"))
    )
    (net (code "37") (name "Net-(U11-CAPP)") (class "Default")
      (node (ref "C70") (pin "1") (pinfunction "1_1") (pintype "passive"))
      (node (ref "U11") (pin "2") (pinfunction "CAPP_2") (pintype "power_in"))
    )
    (net (code "38") (name "Net-(U11-GPIO3)") (class "Default")
      (node (ref "TP42") (pin "1") (pinfunction "1_1") (pintype "passive"))
      (node (ref "U11") (pin "15") (pinfunction "GPIO3_15") (pintype "bidirectional"))
    )
    (net (code "39") (name "Net-(U11-LDOO)") (class "Default")
      (node (ref "C78") (pin "1") (pinfunction "1_1") (pintype "passive"))
      (node (ref "U11") (pin "26") (pinfunction "LDOO_26") (pintype "power_in"))
    )
    (net (code "40") (name "Net-(U11-OUTL)") (class "Default")
      (node (ref "R50") (pin "1") (pinfunction "1_1") (pintype "passive"))
      (node (ref "U11") (pin "6") (pinfunction "OUTL_6") (pintype "passive"))
    )
    (net (code "41") (name "Net-(U11-OUTR)") (class "Default")
      (node (ref "R52") (pin "1") (pinfunction "1_1") (pintype "passive"))
      (node (ref "U11") (pin "7") (pinfunction "OUTR_7") (pintype "passive"))
    )
    (net (code "42") (name "Net-(U11-VCOM)") (class "Default")
      (node (ref "R54") (pin "2") (pinfunction "2_2") (pintype "passive"))
      (node (ref "U11") (pin "10") (pinfunction "VCOM_10") (pintype "power_in"))
    )
    (net (code "43") (name "Net-(U11-VNEG)") (class "Default")
      (node (ref "C77") (pin "1") (pinfunction "1_1") (pintype "passive"))
      (node (ref "U11") (pin "5") (pinfunction "VNEG_5") (pintype "power_in"))
    )
    (net (code "44") (name "Net-(U12-CAPM)") (class "Default")
      (node (ref "C87") (pin "2") (pinfunction "2_2") (pintype "passive"))
      (node (ref "U12") (pin "4") (pinfunction "CAPM_4") (pintype "power_in"))
    )
    (net (code "45") (name "Net-(U12-CAPP)") (class "Default")
      (node (ref "C87") (pin "1") (pinfunction "1_1") (pintype "passive"))
      (node (ref "U12") (pin "2") (pinfunction "CAPP_2") (pintype "power_in"))
    )
    (net (code "46") (name "Net-(U12-GPIO3)") (class "Default")
      (node (ref "TP43") (pin "1") (pinfunction "1_1") (pintype "passive"))
      (node (ref "U12") (pin "15") (pinfunction "GPIO3_15") (pintype "bidirectional"))
    )
    (net (code "47") (name "Net-(U12-LDOO)") (class "Default")
      (node (ref "C90") (pin "1") (pinfunction "1_1") (pintype "passive"))
      (node (ref "U12") (pin "26") (pinfunction "LDOO_26") (pintype "power_in"))
    )
    (net (code "48") (name "Net-(U12-OUTL)") (class "Default")
      (node (ref "R55") (pin "1") (pinfunction "1_1") (pintype "passive"))
      (node (ref "U12") (pin "6") (pinfunction "OUTL_6") (pintype "passive"))
    )
    (net (code "49") (name "Net-(U12-OUTR)") (class "Default")
      (node (ref "R57") (pin "1") (pinfunction "1_1") (pintype "passive"))
      (node (ref "U12") (pin "7") (pinfunction "OUTR_7") (pintype "passive"))
    )
    (net (code "50") (name "Net-(U12-VCOM)") (class "Default")
      (node (ref "R60") (pin "2") (pinfunction "2_2") (pintype "passive"))
      (node (ref "U12") (pin "10") (pinfunction "VCOM_10") (pintype "power_in"))
    )
    (net (code "51") (name "Net-(U12-VNEG)") (class "Default")
      (node (ref "C89") (pin "1") (pinfunction "1_1") (pintype "passive"))
      (node (ref "U12") (pin "5") (pinfunction "VNEG_5") (pintype "power_in"))
    )
    (net (code "52") (name "Net-(U13-CAPM)") (class "Default")
      (node (ref "C88") (pin "2") (pinfunction "2_2") (pintype "passive"))
      (node (ref "U13") (pin "4") (pinfunction "CAPM_4") (pintype "power_in"))
    )
    (net (code "53") (name "Net-(U13-CAPP)") (class "Default")
      (node (ref "C88") (pin "1") (pinfunction "1_1") (pintype "passive"))
      (node (ref "U13") (pin "2") (pinfunction "CAPP_2") (pintype "power_in"))
    )
    (net (code "54") (name "Net-(U13-GPIO3)") (class "Default")
      (node (ref "TP44") (pin "1") (pinfunction "1_1") (pintype "passive"))
      (node (ref "U13") (pin "15") (pinfunction "GPIO3_15") (pintype "bidirectional"))
    )
    (net (code "55") (name "Net-(U13-LDOO)") (class "Default")
      (node (ref "C96") (pin "1") (pinfunction "1_1") (pintype "passive"))
      (node (ref "U13") (pin "26") (pinfunction "LDOO_26") (pintype "power_in"))
    )
    (net (code "56") (name "Net-(U13-OUTL)") (class "Default")
      (node (ref "R56") (pin "1") (pinfunction "1_1") (pintype "passive"))
      (node (ref "U13") (pin "6") (pinfunction "OUTL_6") (pintype "passive"))
    )
    (net (code "57") (name "Net-(U13-OUTR)") (class "Default")
      (node (ref "R58") (pin "1") (pinfunction "1_1") (pintype "passive"))
      (node (ref "U13") (pin "7") (pinfunction "OUTR_7") (pintype "passive"))
    )
    (net (code "58") (name "Net-(U13-VCOM)") (class "Default")
      (node (ref "R61") (pin "2") (pinfunction "2_2") (pintype "passive"))
      (node (ref "U13") (pin "10") (pinfunction "VCOM_10") (pintype "power_in"))
    )
    (net (code "59") (name "Net-(U13-VNEG)") (class "Default")
      (node (ref "C95") (pin "1") (pinfunction "1_1") (pintype "passive"))
      (node (ref "U13") (pin "5") (pinfunction "VNEG_5") (pintype "power_in"))
    )
    (net (code "60") (name "unconnected-(U10-GPIO4-Pad14)") (class "Default")
      (node (ref "U10") (pin "14") (pinfunction "GPIO4_14") (pintype "bidirectional+no_connect"))
    )
    (net (code "61") (name "unconnected-(U10-GPIO5-Pad13)") (class "Default")
      (node (ref "U10") (pin "13") (pinfunction "GPIO5_13") (pintype "bidirectional+no_connect"))
    )
    (net (code "62") (name "unconnected-(U11-GPIO4-Pad14)") (class "Default")
      (node (ref "U11") (pin "14") (pinfunction "GPIO4_14") (pintype "bidirectional+no_connect"))
    )
    (net (code "63") (name "unconnected-(U11-GPIO5-Pad13)") (class "Default")
      (node (ref "U11") (pin "13") (pinfunction "GPIO5_13") (pintype "bidirectional+no_connect"))
    )
    (net (code "64") (name "unconnected-(U12-GPIO4-Pad14)") (class "Default")
      (node (ref "U12") (pin "14") (pinfunction "GPIO4_14") (pintype "bidirectional+no_connect"))
    )
    (net (code "65") (name "unconnected-(U12-GPIO5-Pad13)") (class "Default")
      (node (ref "U12") (pin "13") (pinfunction "GPIO5_13") (pintype "bidirectional+no_connect"))
    )
    (net (code "66") (name "unconnected-(U13-GPIO4-Pad14)") (class "Default")
      (node (ref "U13") (pin "14") (pinfunction "GPIO4_14") (pintype "bidirectional+no_connect"))
    )
    (net (code "67") (name "unconnected-(U13-GPIO5-Pad13)") (class "Default")
      (node (ref "U13") (pin "13") (pinfunction "GPIO5_13") (pintype "bidirectional+no_connect"))
    )
  )
)
